# motherboard.net
KiCad netlist of a schematic drawn in EAGLE
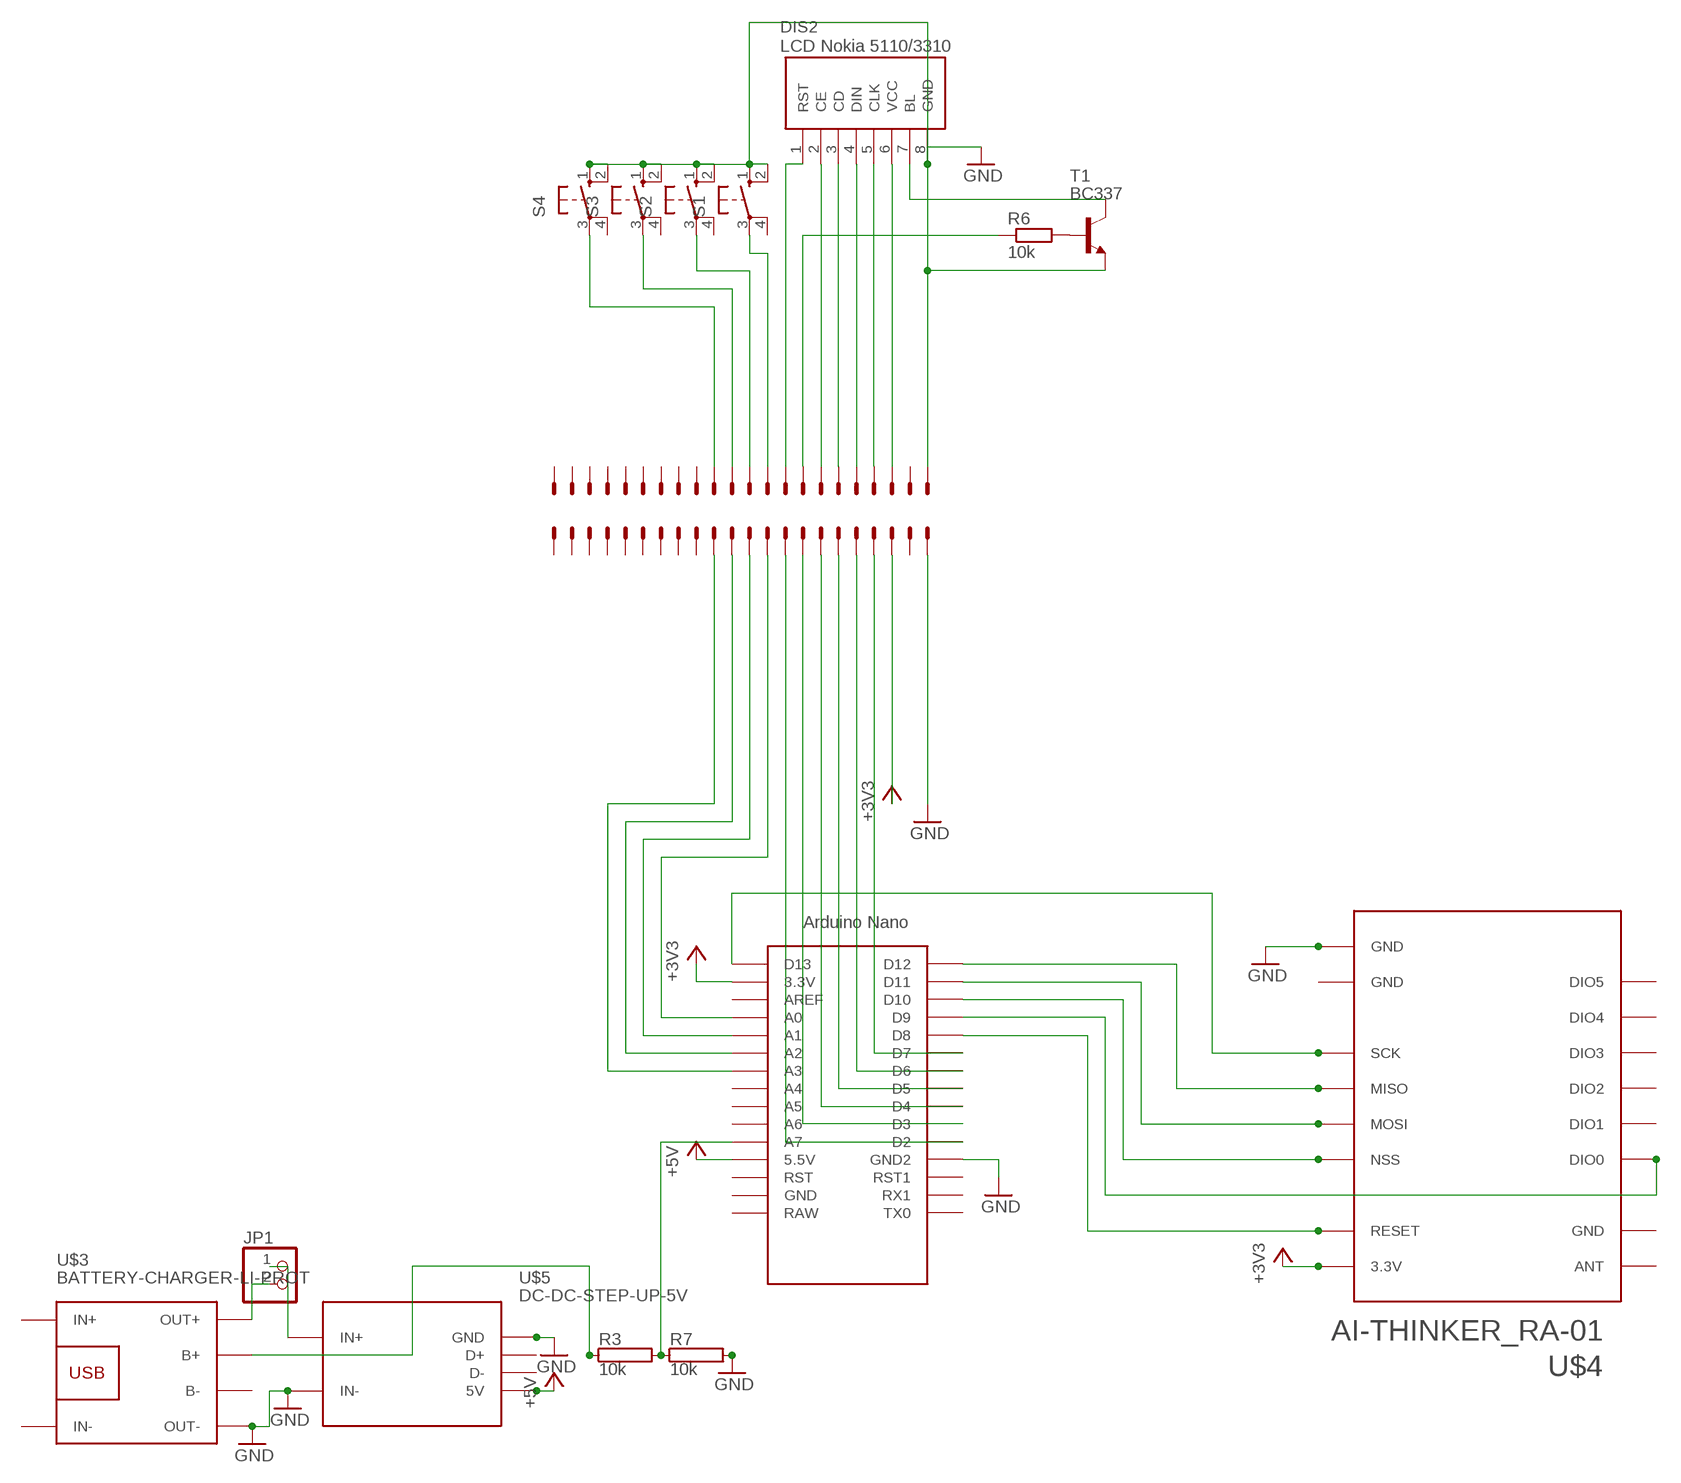
[diagram p0: schematic, sheet 1]

(export (version "E")
  (design (tool "Eeschema 10.0.6"))
  (components
    (comp (ref "DIS2")
      (value "NOKIA5110")
      (footprint "eagle-import:NOKIA5110")
      (libsource (lib "eagle-import") (part "NOKIA5110"))
    )
    (comp (ref "J1")
      (value "XF2L-2235-1")
      (footprint "eagle-import:XF2L-2235-1")
      (fields (field (name "MPN") "XF2L-2235-1A"))
      (libsource (lib "eagle-import") (part "XF2-22?35-1L"))
    )
    (comp (ref "J2")
      (value "XF2L-2235-1")
      (footprint "eagle-import:XF2L-2235-1")
      (fields (field (name "MPN") "XF2L-2235-1A"))
      (libsource (lib "eagle-import") (part "XF2-22?35-1L"))
    )
    (comp (ref "JP1")
      (value "PINHD-1X2/90")
      (footprint "eagle-import:1X02_90")
      (libsource (lib "eagle-import") (part "PINHD-1X2/90"))
    )
    (comp (ref "R3")
      (value "10k")
      (footprint "eagle-import:AC01")
      (libsource (lib "eagle-import") (part "RAC01"))
    )
    (comp (ref "R6")
      (value "10k")
      (footprint "eagle-import:0204_5")
      (libsource (lib "eagle-import") (part "R-EU_0204/5"))
    )
    (comp (ref "R7")
      (value "10k")
      (footprint "eagle-import:AC01")
      (libsource (lib "eagle-import") (part "RAC01"))
    )
    (comp (ref "S1")
      (value "10-XX")
      (footprint "eagle-import:B3F-10XX")
      (fields (field (name "MPN") "B3F-1000"))
      (libsource (lib "eagle-import") (part "10-XX"))
    )
    (comp (ref "S2")
      (value "10-XX")
      (footprint "eagle-import:B3F-10XX")
      (fields (field (name "MPN") "B3F-1000"))
      (libsource (lib "eagle-import") (part "10-XX"))
    )
    (comp (ref "S3")
      (value "10-XX")
      (footprint "eagle-import:B3F-10XX")
      (fields (field (name "MPN") "B3F-1000"))
      (libsource (lib "eagle-import") (part "10-XX"))
    )
    (comp (ref "S4")
      (value "10-XX")
      (footprint "eagle-import:B3F-10XX")
      (fields (field (name "MPN") "B3F-1000"))
      (libsource (lib "eagle-import") (part "10-XX"))
    )
    (comp (ref "T1")
      (value "BC337")
      (footprint "eagle-import:TO92")
      (libsource (lib "eagle-import") (part "BC337"))
    )
    (comp (ref "U$1")
      (value "NANO")
      (footprint "eagle-import:NANO")
      (libsource (lib "eagle-import") (part "NANO"))
    )
    (comp (ref "U$3")
      (value "BATTERY-CHARGER-LI-PROT")
      (footprint "eagle-import:BATTERY-CHARGER-LI-PROT")
      (libsource (lib "eagle-import") (part "BATTERY-CHARGER-LI-PROT"))
    )
    (comp (ref "U$4")
      (value "AI-THINKER_RA-01")
      (footprint "eagle-import:AI-THINKER_RA-01")
      (libsource (lib "eagle-import") (part "AI-THINKER_RA-01"))
    )
    (comp (ref "U$5")
      (value "DC-DC-STEP-UP-5V")
      (footprint "eagle-import:DC-DC-STEP-UP-5V")
      (libsource (lib "eagle-import") (part "DC-DC-STEP-UP-5V"))
    )
  )
  (nets
    (net (code "1") (name "+3V3") (class "Default")
      (node (ref "J1") (pin "20") (pinfunction "MS_20") (pintype "passive"))
      (node (ref "U$1") (pin "3.3V") (pinfunction "3.3V_3.3V") (pintype "bidirectional"))
      (node (ref "U$4") (pin "P$3") (pinfunction "3.3V_P$3") (pintype "bidirectional"))
    )
    (net (code "2") (name "+5V") (class "Default")
      (node (ref "U$1") (pin "5V") (pinfunction "5.5V_5V") (pintype "bidirectional"))
      (node (ref "U$5") (pin "5V") (pinfunction "5V_5V") (pintype "bidirectional"))
    )
    (net (code "3") (name "GND") (class "Default")
      (node (ref "DIS2") (pin "8") (pinfunction "GND_8") (pintype "power_in"))
      (node (ref "J1") (pin "22") (pinfunction "MS_22") (pintype "passive"))
      (node (ref "J2") (pin "1") (pinfunction "MSV_1") (pintype "passive"))
      (node (ref "R7") (pin "2") (pinfunction "2_2") (pintype "passive"))
      (node (ref "S1") (pin "1") (pinfunction "S_1") (pintype "passive"))
      (node (ref "S1") (pin "2") (pinfunction "S1_2") (pintype "passive"))
      (node (ref "S2") (pin "1") (pinfunction "S_1") (pintype "passive"))
      (node (ref "S2") (pin "2") (pinfunction "S1_2") (pintype "passive"))
      (node (ref "S3") (pin "1") (pinfunction "S_1") (pintype "passive"))
      (node (ref "S3") (pin "2") (pinfunction "S1_2") (pintype "passive"))
      (node (ref "S4") (pin "1") (pinfunction "S_1") (pintype "passive"))
      (node (ref "S4") (pin "2") (pinfunction "S1_2") (pintype "passive"))
      (node (ref "T1") (pin "1") (pinfunction "E_1") (pintype "passive"))
      (node (ref "U$1") (pin "GND1") (pinfunction "GND2_GND1") (pintype "bidirectional"))
      (node (ref "U$3") (pin "OUT-") (pinfunction "OUT-_OUT-") (pintype "bidirectional"))
      (node (ref "U$4") (pin "P$16") (pinfunction "GND_P$16") (pintype "bidirectional"))
      (node (ref "U$5") (pin "GND") (pinfunction "GND_GND") (pintype "bidirectional"))
      (node (ref "U$5") (pin "IN-") (pinfunction "IN-_IN-") (pintype "power_in"))
    )
    (net (code "4") (name "Net-(DIS2-BL)") (class "Default")
      (node (ref "DIS2") (pin "7") (pinfunction "BL_7") (pintype "bidirectional"))
      (node (ref "T1") (pin "3") (pinfunction "C_3") (pintype "passive"))
    )
    (net (code "5") (name "Net-(DIS2-CD)") (class "Default")
      (node (ref "DIS2") (pin "3") (pinfunction "CD_3") (pintype "bidirectional"))
      (node (ref "J2") (pin "6") (pinfunction "MS_6") (pintype "passive"))
    )
    (net (code "6") (name "Net-(DIS2-CE)") (class "Default")
      (node (ref "DIS2") (pin "2") (pinfunction "CE_2") (pintype "bidirectional"))
      (node (ref "J2") (pin "7") (pinfunction "MS_7") (pintype "passive"))
    )
    (net (code "7") (name "Net-(DIS2-CLK)") (class "Default")
      (node (ref "DIS2") (pin "5") (pinfunction "CLK_5") (pintype "bidirectional"))
      (node (ref "J2") (pin "4") (pinfunction "MS_4") (pintype "passive"))
    )
    (net (code "8") (name "Net-(DIS2-DIN)") (class "Default")
      (node (ref "DIS2") (pin "4") (pinfunction "DIN_4") (pintype "bidirectional"))
      (node (ref "J2") (pin "5") (pinfunction "MS_5") (pintype "passive"))
    )
    (net (code "9") (name "Net-(DIS2-RST)") (class "Default")
      (node (ref "DIS2") (pin "1") (pinfunction "RST_1") (pintype "bidirectional"))
      (node (ref "J2") (pin "9") (pinfunction "MS_9") (pintype "passive"))
    )
    (net (code "10") (name "Net-(DIS2-VCC)") (class "Default")
      (node (ref "DIS2") (pin "6") (pinfunction "VCC_6") (pintype "power_in"))
      (node (ref "J2") (pin "3") (pinfunction "MS_3") (pintype "passive"))
    )
    (net (code "11") (name "Net-(J1B-MS)") (class "Default")
      (node (ref "J1") (pin "10") (pinfunction "MS_10") (pintype "passive"))
      (node (ref "U$1") (pin "A3") (pinfunction "A3_A3") (pintype "bidirectional"))
    )
    (net (code "12") (name "Net-(J1C-MS)") (class "Default")
      (node (ref "J1") (pin "11") (pinfunction "MS_11") (pintype "passive"))
      (node (ref "U$1") (pin "A2") (pinfunction "A2_A2") (pintype "bidirectional"))
    )
    (net (code "13") (name "Net-(J1D-MS)") (class "Default")
      (node (ref "J1") (pin "12") (pinfunction "MS_12") (pintype "passive"))
      (node (ref "U$1") (pin "A1") (pinfunction "A1_A1") (pintype "bidirectional"))
    )
    (net (code "14") (name "Net-(J1E-MS)") (class "Default")
      (node (ref "J1") (pin "13") (pinfunction "MS_13") (pintype "passive"))
      (node (ref "U$1") (pin "A0") (pinfunction "A0_A0") (pintype "bidirectional"))
    )
    (net (code "15") (name "Net-(J1F-MS)") (class "Default")
      (node (ref "J1") (pin "14") (pinfunction "MS_14") (pintype "passive"))
      (node (ref "U$1") (pin "D2") (pinfunction "D2_D2") (pintype "bidirectional"))
    )
    (net (code "16") (name "Net-(J1G-MS)") (class "Default")
      (node (ref "J1") (pin "15") (pinfunction "MS_15") (pintype "passive"))
      (node (ref "U$1") (pin "D3") (pinfunction "D3_D3") (pintype "bidirectional"))
    )
    (net (code "17") (name "Net-(J1H-MS)") (class "Default")
      (node (ref "J1") (pin "16") (pinfunction "MS_16") (pintype "passive"))
      (node (ref "U$1") (pin "D4") (pinfunction "D4_D4") (pintype "bidirectional"))
    )
    (net (code "18") (name "Net-(J1I-MS)") (class "Default")
      (node (ref "J1") (pin "17") (pinfunction "MS_17") (pintype "passive"))
      (node (ref "U$1") (pin "D5") (pinfunction "D5_D5") (pintype "bidirectional"))
    )
    (net (code "19") (name "Net-(J1J-MS)") (class "Default")
      (node (ref "J1") (pin "18") (pinfunction "MS_18") (pintype "passive"))
      (node (ref "U$1") (pin "D6") (pinfunction "D6_D6") (pintype "bidirectional"))
    )
    (net (code "20") (name "Net-(J1K-MS)") (class "Default")
      (node (ref "J1") (pin "19") (pinfunction "MS_19") (pintype "passive"))
      (node (ref "U$1") (pin "D7") (pinfunction "D7_D7") (pintype "bidirectional"))
    )
    (net (code "21") (name "Net-(J2B-MS)") (class "Default")
      (node (ref "J2") (pin "10") (pinfunction "MS_10") (pintype "passive"))
      (node (ref "S1") (pin "3") (pinfunction "P_3") (pintype "passive"))
    )
    (net (code "22") (name "Net-(J2C-MS)") (class "Default")
      (node (ref "J2") (pin "11") (pinfunction "MS_11") (pintype "passive"))
      (node (ref "S2") (pin "3") (pinfunction "P_3") (pintype "passive"))
    )
    (net (code "23") (name "Net-(J2D-MS)") (class "Default")
      (node (ref "J2") (pin "12") (pinfunction "MS_12") (pintype "passive"))
      (node (ref "S3") (pin "3") (pinfunction "P_3") (pintype "passive"))
    )
    (net (code "24") (name "Net-(J2E-MS)") (class "Default")
      (node (ref "J2") (pin "13") (pinfunction "MS_13") (pintype "passive"))
      (node (ref "S4") (pin "3") (pinfunction "P_3") (pintype "passive"))
    )
    (net (code "25") (name "Net-(J2U-MS)") (class "Default")
      (node (ref "J2") (pin "8") (pinfunction "MS_8") (pintype "passive"))
      (node (ref "R6") (pin "1") (pinfunction "1_1") (pintype "passive"))
    )
    (net (code "26") (name "Net-(JP1-Pad1)") (class "Default")
      (node (ref "JP1") (pin "1") (pinfunction "1_1") (pintype "passive"))
      (node (ref "U$5") (pin "IN+") (pinfunction "IN+_IN+") (pintype "power_in"))
    )
    (net (code "27") (name "Net-(JP1-Pad2)") (class "Default")
      (node (ref "JP1") (pin "2") (pinfunction "2_2") (pintype "passive"))
      (node (ref "U$3") (pin "OUT+") (pinfunction "OUT+_OUT+") (pintype "bidirectional"))
    )
    (net (code "28") (name "Net-(R3-Pad1)") (class "Default")
      (node (ref "R3") (pin "1") (pinfunction "1_1") (pintype "passive"))
      (node (ref "U$3") (pin "B+") (pinfunction "B+_B+") (pintype "bidirectional"))
    )
    (net (code "29") (name "Net-(R3-Pad2)") (class "Default")
      (node (ref "R3") (pin "2") (pinfunction "2_2") (pintype "passive"))
      (node (ref "R7") (pin "1") (pinfunction "1_1") (pintype "passive"))
      (node (ref "U$1") (pin "A7") (pinfunction "A7_A7") (pintype "bidirectional"))
    )
    (net (code "30") (name "Net-(T1-B)") (class "Default")
      (node (ref "R6") (pin "2") (pinfunction "2_2") (pintype "passive"))
      (node (ref "T1") (pin "2") (pinfunction "B_2") (pintype "passive"))
    )
    (net (code "31") (name "Net-(U$4-DIO0)") (class "Default")
      (node (ref "U$1") (pin "D9") (pinfunction "D9_D9") (pintype "bidirectional"))
      (node (ref "U$4") (pin "P$5") (pinfunction "DIO0_P$5") (pintype "bidirectional"))
    )
    (net (code "32") (name "Net-(U$4-MISO)") (class "Default")
      (node (ref "U$1") (pin "D12") (pinfunction "D12_D12") (pintype "bidirectional"))
      (node (ref "U$4") (pin "P$13") (pinfunction "MISO_P$13") (pintype "bidirectional"))
    )
    (net (code "33") (name "Net-(U$4-MOSI)") (class "Default")
      (node (ref "U$1") (pin "D11") (pinfunction "D11_D11") (pintype "bidirectional"))
      (node (ref "U$4") (pin "P$14") (pinfunction "MOSI_P$14") (pintype "bidirectional"))
    )
    (net (code "34") (name "Net-(U$4-NSS)") (class "Default")
      (node (ref "U$1") (pin "D10") (pinfunction "D10_D10") (pintype "bidirectional"))
      (node (ref "U$4") (pin "P$15") (pinfunction "NSS_P$15") (pintype "bidirectional"))
    )
    (net (code "35") (name "Net-(U$4-RESET)") (class "Default")
      (node (ref "U$1") (pin "D8") (pinfunction "D8_D8") (pintype "bidirectional"))
      (node (ref "U$4") (pin "P$4") (pinfunction "RESET_P$4") (pintype "bidirectional"))
    )
    (net (code "36") (name "Net-(U$4-SCK)") (class "Default")
      (node (ref "U$1") (pin "D13") (pinfunction "D13_D13") (pintype "bidirectional"))
      (node (ref "U$4") (pin "P$12") (pinfunction "SCK_P$12") (pintype "bidirectional"))
    )
    (net (code "37") (name "unconnected-(J1A-MSV-Pad1)") (class "Default")
      (node (ref "J1") (pin "1") (pinfunction "MSV_1") (pintype "passive"))
    )
    (net (code "38") (name "unconnected-(J1L-MS-Pad2)") (class "Default")
      (node (ref "J1") (pin "2") (pinfunction "MS_2") (pintype "passive"))
    )
    (net (code "39") (name "unconnected-(J1N-MS-Pad21)") (class "Default")
      (node (ref "J1") (pin "21") (pinfunction "MS_21") (pintype "passive"))
    )
    (net (code "40") (name "unconnected-(J1P-MS-Pad3)") (class "Default")
      (node (ref "J1") (pin "3") (pinfunction "MS_3") (pintype "passive"))
    )
    (net (code "41") (name "unconnected-(J1Q-MS-Pad4)") (class "Default")
      (node (ref "J1") (pin "4") (pinfunction "MS_4") (pintype "passive"))
    )
    (net (code "42") (name "unconnected-(J1R-MS-Pad5)") (class "Default")
      (node (ref "J1") (pin "5") (pinfunction "MS_5") (pintype "passive"))
    )
    (net (code "43") (name "unconnected-(J1S-MS-Pad6)") (class "Default")
      (node (ref "J1") (pin "6") (pinfunction "MS_6") (pintype "passive"))
    )
    (net (code "44") (name "unconnected-(J1T-MS-Pad7)") (class "Default")
      (node (ref "J1") (pin "7") (pinfunction "MS_7") (pintype "passive"))
    )
    (net (code "45") (name "unconnected-(J1U-MS-Pad8)") (class "Default")
      (node (ref "J1") (pin "8") (pinfunction "MS_8") (pintype "passive"))
    )
    (net (code "46") (name "unconnected-(J1V-MS-Pad9)") (class "Default")
      (node (ref "J1") (pin "9") (pinfunction "MS_9") (pintype "passive"))
    )
    (net (code "47") (name "unconnected-(J2F-MS-Pad14)") (class "Default")
      (node (ref "J2") (pin "14") (pinfunction "MS_14") (pintype "passive"))
    )
    (net (code "48") (name "unconnected-(J2G-MS-Pad15)") (class "Default")
      (node (ref "J2") (pin "15") (pinfunction "MS_15") (pintype "passive"))
    )
    (net (code "49") (name "unconnected-(J2H-MS-Pad16)") (class "Default")
      (node (ref "J2") (pin "16") (pinfunction "MS_16") (pintype "passive"))
    )
    (net (code "50") (name "unconnected-(J2I-MS-Pad17)") (class "Default")
      (node (ref "J2") (pin "17") (pinfunction "MS_17") (pintype "passive"))
    )
    (net (code "51") (name "unconnected-(J2J-MS-Pad18)") (class "Default")
      (node (ref "J2") (pin "18") (pinfunction "MS_18") (pintype "passive"))
    )
    (net (code "52") (name "unconnected-(J2K-MS-Pad19)") (class "Default")
      (node (ref "J2") (pin "19") (pinfunction "MS_19") (pintype "passive"))
    )
    (net (code "53") (name "unconnected-(J2L-MS-Pad2)") (class "Default")
      (node (ref "J2") (pin "2") (pinfunction "MS_2") (pintype "passive"))
    )
    (net (code "54") (name "unconnected-(J2M-MS-Pad20)") (class "Default")
      (node (ref "J2") (pin "20") (pinfunction "MS_20") (pintype "passive"))
    )
    (net (code "55") (name "unconnected-(J2N-MS-Pad21)") (class "Default")
      (node (ref "J2") (pin "21") (pinfunction "MS_21") (pintype "passive"))
    )
    (net (code "56") (name "unconnected-(J2O-MS-Pad22)") (class "Default")
      (node (ref "J2") (pin "22") (pinfunction "MS_22") (pintype "passive"))
    )
    (net (code "57") (name "unconnected-(S1-P1-Pad4)") (class "Default")
      (node (ref "S1") (pin "4") (pinfunction "P1_4") (pintype "passive"))
    )
    (net (code "58") (name "unconnected-(S2-P1-Pad4)") (class "Default")
      (node (ref "S2") (pin "4") (pinfunction "P1_4") (pintype "passive"))
    )
    (net (code "59") (name "unconnected-(S3-P1-Pad4)") (class "Default")
      (node (ref "S3") (pin "4") (pinfunction "P1_4") (pintype "passive"))
    )
    (net (code "60") (name "unconnected-(S4-P1-Pad4)") (class "Default")
      (node (ref "S4") (pin "4") (pinfunction "P1_4") (pintype "passive"))
    )
    (net (code "61") (name "unconnected-(U$1-PadA4)") (class "Default")
      (node (ref "U$1") (pin "A4") (pinfunction "A4_A4") (pintype "bidirectional"))
    )
    (net (code "62") (name "unconnected-(U$1-PadA5)") (class "Default")
      (node (ref "U$1") (pin "A5") (pinfunction "A5_A5") (pintype "bidirectional"))
    )
    (net (code "63") (name "unconnected-(U$1-PadA6)") (class "Default")
      (node (ref "U$1") (pin "A6") (pinfunction "A6_A6") (pintype "bidirectional"))
    )
    (net (code "64") (name "unconnected-(U$1-PadAREF)") (class "Default")
      (node (ref "U$1") (pin "AREF") (pinfunction "AREF_AREF") (pintype "bidirectional"))
    )
    (net (code "65") (name "unconnected-(U$1-PadGND)") (class "Default")
      (node (ref "U$1") (pin "GND") (pinfunction "GND_GND") (pintype "bidirectional"))
    )
    (net (code "66") (name "unconnected-(U$1-PadICSP1)") (class "Default")
      (node (ref "U$1") (pin "ICSP1") (pinfunction "ICSP1_ICSP1") (pintype "bidirectional"))
    )
    (net (code "67") (name "unconnected-(U$1-PadICSP2)") (class "Default")
      (node (ref "U$1") (pin "ICSP2") (pinfunction "ICSP2_ICSP2") (pintype "bidirectional"))
    )
    (net (code "68") (name "unconnected-(U$1-PadICSP3)") (class "Default")
      (node (ref "U$1") (pin "ICSP3") (pinfunction "ICSP3_ICSP3") (pintype "bidirectional"))
    )
    (net (code "69") (name "unconnected-(U$1-PadICSP4)") (class "Default")
      (node (ref "U$1") (pin "ICSP4") (pinfunction "ICSP4_ICSP4") (pintype "bidirectional"))
    )
    (net (code "70") (name "unconnected-(U$1-PadICSP5)") (class "Default")
      (node (ref "U$1") (pin "ICSP5") (pinfunction "ICSP5_ICSP5") (pintype "bidirectional"))
    )
    (net (code "71") (name "unconnected-(U$1-PadICSP6)") (class "Default")
      (node (ref "U$1") (pin "ICSP6") (pinfunction "ICSP6_ICSP6") (pintype "bidirectional"))
    )
    (net (code "72") (name "unconnected-(U$1-PadRAW)") (class "Default")
      (node (ref "U$1") (pin "RAW") (pinfunction "RAW_RAW") (pintype "bidirectional"))
    )
    (net (code "73") (name "unconnected-(U$1-PadRST)") (class "Default")
      (node (ref "U$1") (pin "RST") (pinfunction "RST_RST") (pintype "bidirectional"))
    )
    (net (code "74") (name "unconnected-(U$1-PadRST1)") (class "Default")
      (node (ref "U$1") (pin "RST1") (pinfunction "RST1_RST1") (pintype "bidirectional"))
    )
    (net (code "75") (name "unconnected-(U$1-PadRX1)") (class "Default")
      (node (ref "U$1") (pin "RX1") (pinfunction "RX1_RX1") (pintype "bidirectional"))
    )
    (net (code "76") (name "unconnected-(U$1-PadTX0)") (class "Default")
      (node (ref "U$1") (pin "TX0") (pinfunction "TX0_TX0") (pintype "bidirectional"))
    )
    (net (code "77") (name "unconnected-(U$3-PadB-)") (class "Default")
      (node (ref "U$3") (pin "B-") (pinfunction "B-_B-") (pintype "bidirectional"))
    )
    (net (code "78") (name "unconnected-(U$3-PadIN+)") (class "Default")
      (node (ref "U$3") (pin "IN+") (pinfunction "IN+_IN+") (pintype "bidirectional"))
    )
    (net (code "79") (name "unconnected-(U$3-PadIN-)") (class "Default")
      (node (ref "U$3") (pin "IN-") (pinfunction "IN-_IN-") (pintype "bidirectional"))
    )
    (net (code "80") (name "unconnected-(U$4-ANT-PadP$1)") (class "Default")
      (node (ref "U$4") (pin "P$1") (pinfunction "ANT_P$1") (pintype "bidirectional"))
    )
    (net (code "81") (name "unconnected-(U$4-DIO1-PadP$6)") (class "Default")
      (node (ref "U$4") (pin "P$6") (pinfunction "DIO1_P$6") (pintype "bidirectional"))
    )
    (net (code "82") (name "unconnected-(U$4-DIO2-PadP$7)") (class "Default")
      (node (ref "U$4") (pin "P$7") (pinfunction "DIO2_P$7") (pintype "bidirectional"))
    )
    (net (code "83") (name "unconnected-(U$4-DIO3-PadP$8)") (class "Default")
      (node (ref "U$4") (pin "P$8") (pinfunction "DIO3_P$8") (pintype "bidirectional"))
    )
    (net (code "84") (name "unconnected-(U$4-DIO4-PadP$10)") (class "Default")
      (node (ref "U$4") (pin "P$10") (pinfunction "DIO4_P$10") (pintype "bidirectional"))
    )
    (net (code "85") (name "unconnected-(U$4-DIO5-PadP$11)") (class "Default")
      (node (ref "U$4") (pin "P$11") (pinfunction "DIO5_P$11") (pintype "bidirectional"))
    )
    (net (code "86") (name "unconnected-(U$4-GND-PadP$2)") (class "Default")
      (node (ref "U$4") (pin "P$2") (pinfunction "GND_P$2") (pintype "bidirectional"))
    )
    (net (code "87") (name "unconnected-(U$4-GND-PadP$9)") (class "Default")
      (node (ref "U$4") (pin "P$9") (pinfunction "GND_P$9") (pintype "bidirectional"))
    )
    (net (code "88") (name "unconnected-(U$5-PadD+)") (class "Default")
      (node (ref "U$5") (pin "D+") (pinfunction "D+_D+") (pintype "bidirectional"))
    )
    (net (code "89") (name "unconnected-(U$5-PadD-)") (class "Default")
      (node (ref "U$5") (pin "D-") (pinfunction "D-_D-") (pintype "bidirectional"))
    )
  )
)
